# USB-nano.net
KiCad netlist of a schematic drawn in EAGLE
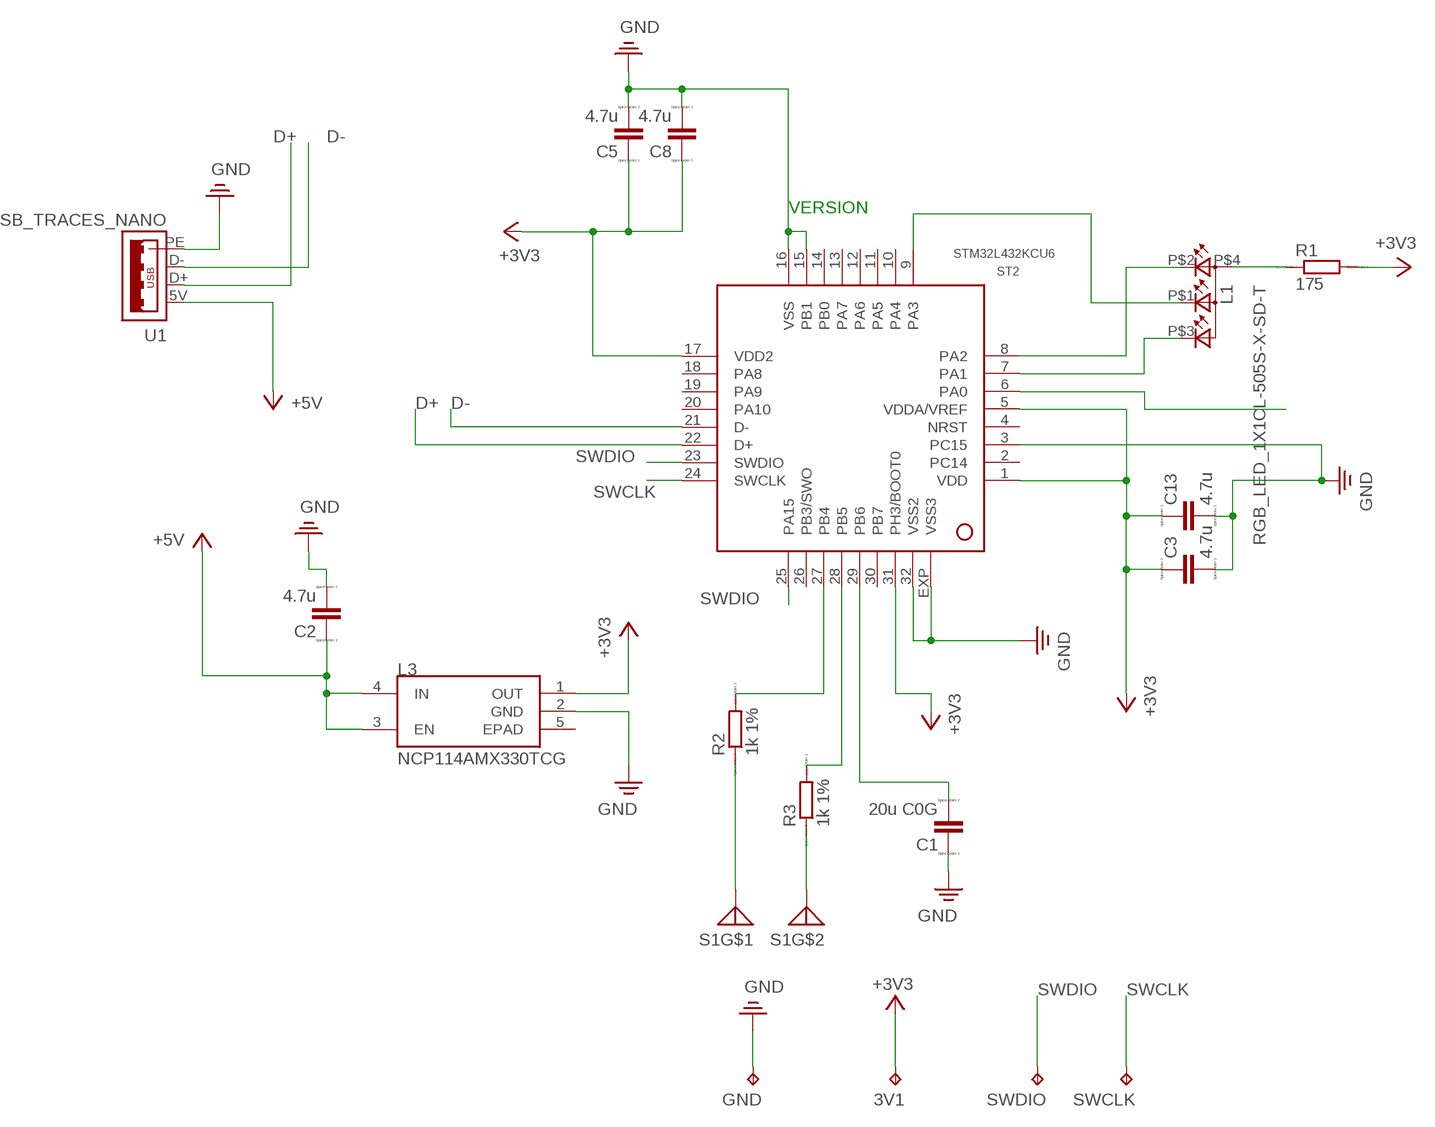
[diagram p0: schematic, sheet 1]

(export (version "E")
  (design (tool "Eeschema 10.0.6"))
  (components
    (comp (ref "3V1")
      (value "TEST_POINT")
      (footprint "eagle-import:B1,27")
      (libsource (lib "eagle-import") (part "TEST_POINT"))
    )
    (comp (ref "C1")
      (value "20u C0G")
      (footprint "eagle-import:C0402")
      (libsource (lib "eagle-import") (part "CAPACITOR"))
    )
    (comp (ref "C2")
      (value "4.7u")
      (footprint "eagle-import:C0402")
      (libsource (lib "eagle-import") (part "CAPACITOR"))
    )
    (comp (ref "C3")
      (value "4.7u")
      (footprint "eagle-import:C0402")
      (libsource (lib "eagle-import") (part "CAPACITOR"))
    )
    (comp (ref "C5")
      (value "4.7u")
      (footprint "eagle-import:C0402")
      (libsource (lib "eagle-import") (part "CAPACITOR"))
    )
    (comp (ref "C8")
      (value "4.7u")
      (footprint "eagle-import:C0402")
      (libsource (lib "eagle-import") (part "CAPACITOR"))
    )
    (comp (ref "C13")
      (value "4.7u")
      (footprint "eagle-import:C0402")
      (libsource (lib "eagle-import") (part "CAPACITOR"))
    )
    (comp (ref "GND")
      (value "TEST_POINT")
      (footprint "eagle-import:B1,27")
      (libsource (lib "eagle-import") (part "TEST_POINT"))
    )
    (comp (ref "L1")
      (value "RGB_LED_1X1CL-505S-X-SD-T")
      (footprint "eagle-import:CL-505S-X-SD-T")
      (libsource (lib "eagle-import") (part "RGB_LED_1X1CL-505S-X-SD-T"))
    )
    (comp (ref "L3")
      (value "NCP114AMX330TCG")
      (footprint "eagle-import:REG_NCP114AMX330TCG")
      (fields (field (name "MF") "ON Semiconductor"))
      (libsource (lib "eagle-import") (part "NCP114AMX330TCG"))
    )
    (comp (ref "R1")
      (value "175")
      (footprint "eagle-import:R0402")
      (libsource (lib "eagle-import") (part "RESISTOR"))
    )
    (comp (ref "R2")
      (value "1k 1%")
      (footprint "eagle-import:R0402")
      (libsource (lib "eagle-import") (part "RESISTOR"))
    )
    (comp (ref "R3")
      (value "1k 1%")
      (footprint "eagle-import:R0402")
      (libsource (lib "eagle-import") (part "RESISTOR"))
    )
    (comp (ref "S1")
      (value "TOUCH_SENSOR")
      (footprint "eagle-import:SOMU_CAPACITIVE_TOUCH_PAD")
      (libsource (lib "eagle-import") (part "TOUCH_SENSOR"))
    )
    (comp (ref "ST2")
      (value "STM32L432KCU6")
      (footprint "eagle-import:QFN32")
      (libsource (lib "eagle-import") (part "STM32L432KCU6"))
    )
    (comp (ref "SWCLK")
      (value "TEST_POINT")
      (footprint "eagle-import:B1,27")
      (libsource (lib "eagle-import") (part "TEST_POINT"))
    )
    (comp (ref "SWDIO")
      (value "TEST_POINT")
      (footprint "eagle-import:B1,27")
      (libsource (lib "eagle-import") (part "TEST_POINT"))
    )
    (comp (ref "U1")
      (value "USB_TRACES_NANO")
      (footprint "eagle-import:USB_TRACES_NANO")
      (libsource (lib "eagle-import") (part "USB_TRACES_NANO"))
    )
  )
  (nets
    (net (code "1") (name "+3V3") (class "Default")
      (node (ref "3V1") (pin "TP") (pinfunction "TP_TP") (pintype "input"))
      (node (ref "C13") (pin "1") (pinfunction "1_1") (pintype "passive"))
      (node (ref "C3") (pin "1") (pinfunction "1_1") (pintype "passive"))
      (node (ref "C5") (pin "1") (pinfunction "1_1") (pintype "passive"))
      (node (ref "C8") (pin "1") (pinfunction "1_1") (pintype "passive"))
      (node (ref "L3") (pin "1") (pinfunction "OUT_1") (pintype "output"))
      (node (ref "R1") (pin "2") (pinfunction "2_2") (pintype "passive"))
      (node (ref "ST2") (pin "1") (pinfunction "VDD_1") (pintype "bidirectional"))
      (node (ref "ST2") (pin "17") (pinfunction "VDD2_17") (pintype "bidirectional"))
      (node (ref "ST2") (pin "31") (pinfunction "PH3/BOOT0_31") (pintype "bidirectional"))
      (node (ref "ST2") (pin "5") (pinfunction "VDDA/VREF_5") (pintype "bidirectional"))
    )
    (net (code "2") (name "+5V") (class "Default")
      (node (ref "C2") (pin "1") (pinfunction "1_1") (pintype "passive"))
      (node (ref "L3") (pin "3") (pinfunction "EN_3") (pintype "input"))
      (node (ref "L3") (pin "4") (pinfunction "IN_4") (pintype "input"))
      (node (ref "U1") (pin "5V") (pinfunction "1_5V") (pintype "passive"))
    )
    (net (code "3") (name "/D+") (class "Default")
      (node (ref "ST2") (pin "22") (pinfunction "D+_22") (pintype "bidirectional"))
      (node (ref "U1") (pin "D+") (pinfunction "2_D+") (pintype "passive"))
    )
    (net (code "4") (name "/D-") (class "Default")
      (node (ref "ST2") (pin "21") (pinfunction "D-_21") (pintype "bidirectional"))
      (node (ref "U1") (pin "D-") (pinfunction "3_D-") (pintype "passive"))
    )
    (net (code "5") (name "/SWCLK") (class "Default")
      (node (ref "ST2") (pin "24") (pinfunction "SWCLK_24") (pintype "bidirectional"))
      (node (ref "SWCLK") (pin "TP") (pinfunction "TP_TP") (pintype "input"))
    )
    (net (code "6") (name "/SWDIO") (class "Default")
      (node (ref "ST2") (pin "23") (pinfunction "SWDIO_23") (pintype "bidirectional"))
      (node (ref "ST2") (pin "25") (pinfunction "PA15_25") (pintype "bidirectional"))
      (node (ref "SWDIO") (pin "TP") (pinfunction "TP_TP") (pintype "input"))
    )
    (net (code "7") (name "GND") (class "Default")
      (node (ref "C1") (pin "1") (pinfunction "1_1") (pintype "passive"))
      (node (ref "C13") (pin "2") (pinfunction "2_2") (pintype "passive"))
      (node (ref "C2") (pin "2") (pinfunction "2_2") (pintype "passive"))
      (node (ref "C3") (pin "2") (pinfunction "2_2") (pintype "passive"))
      (node (ref "C5") (pin "2") (pinfunction "2_2") (pintype "passive"))
      (node (ref "C8") (pin "2") (pinfunction "2_2") (pintype "passive"))
      (node (ref "GND") (pin "TP") (pinfunction "TP_TP") (pintype "input"))
      (node (ref "L3") (pin "2") (pinfunction "GND_2") (pintype "power_in"))
      (node (ref "ST2") (pin "15") (pinfunction "PB1_15") (pintype "bidirectional"))
      (node (ref "ST2") (pin "16") (pinfunction "VSS_16") (pintype "bidirectional"))
      (node (ref "ST2") (pin "3") (pinfunction "PC15_3") (pintype "bidirectional"))
      (node (ref "ST2") (pin "32") (pinfunction "VSS2_32") (pintype "bidirectional"))
      (node (ref "ST2") (pin "EXP") (pinfunction "VSS3_EXP") (pintype "bidirectional"))
      (node (ref "U1") (pin "PE") (pinfunction "4_PE") (pintype "passive"))
    )
    (net (code "8") (name "Net-(L1-A2)") (class "Default")
      (node (ref "L1") (pin "P$4") (pinfunction "A2_P$4") (pintype "passive"))
      (node (ref "R1") (pin "1") (pinfunction "1_1") (pintype "passive"))
    )
    (net (code "9") (name "Net-(L1-CBLUE)") (class "Default")
      (node (ref "L1") (pin "P$1") (pinfunction "CBLUE_P$1") (pintype "passive"))
      (node (ref "ST2") (pin "9") (pinfunction "PA3_9") (pintype "bidirectional"))
    )
    (net (code "10") (name "Net-(L1-CGREEN)") (class "Default")
      (node (ref "L1") (pin "P$3") (pinfunction "CGREEN_P$3") (pintype "passive"))
      (node (ref "ST2") (pin "7") (pinfunction "PA1_7") (pintype "bidirectional"))
    )
    (net (code "11") (name "Net-(L1-CRED)") (class "Default")
      (node (ref "L1") (pin "P$2") (pinfunction "CRED_P$2") (pintype "passive"))
      (node (ref "ST2") (pin "8") (pinfunction "PA2_8") (pintype "bidirectional"))
    )
    (net (code "12") (name "Net-(R2-Pad1)") (class "Default")
      (node (ref "R2") (pin "1") (pinfunction "1_1") (pintype "passive"))
      (node (ref "S1") (pin "P$1") (pinfunction "1_P$1") (pintype "output"))
      (node (ref "S1") (pin "SENSE") (pinfunction "1_SENSE") (pintype "output"))
    )
    (net (code "13") (name "Net-(R3-Pad1)") (class "Default")
      (node (ref "R3") (pin "1") (pinfunction "1_1") (pintype "passive"))
      (node (ref "S1") (pin "P$2") (pinfunction "1_P$2") (pintype "output"))
      (node (ref "S1") (pin "SENSE2") (pinfunction "1_SENSE2") (pintype "output"))
    )
    (net (code "14") (name "Net-(ST2-PB4)") (class "Default")
      (node (ref "R2") (pin "2") (pinfunction "2_2") (pintype "passive"))
      (node (ref "ST2") (pin "27") (pinfunction "PB4_27") (pintype "bidirectional"))
    )
    (net (code "15") (name "Net-(ST2-PB5)") (class "Default")
      (node (ref "R3") (pin "2") (pinfunction "2_2") (pintype "passive"))
      (node (ref "ST2") (pin "28") (pinfunction "PB5_28") (pintype "bidirectional"))
    )
    (net (code "16") (name "Net-(ST2-PB6)") (class "Default")
      (node (ref "C1") (pin "2") (pinfunction "2_2") (pintype "passive"))
      (node (ref "ST2") (pin "29") (pinfunction "PB6_29") (pintype "bidirectional"))
    )
    (net (code "17") (name "unconnected-(L3-EPAD-Pad5)") (class "Default")
      (node (ref "L3") (pin "5") (pinfunction "EPAD_5") (pintype "passive"))
    )
    (net (code "18") (name "unconnected-(ST2-NRST-Pad4)") (class "Default")
      (node (ref "ST2") (pin "4") (pinfunction "NRST_4") (pintype "bidirectional"))
    )
    (net (code "19") (name "unconnected-(ST2-PA0-Pad6)") (class "Default")
      (node (ref "ST2") (pin "6") (pinfunction "PA0_6") (pintype "bidirectional"))
    )
    (net (code "20") (name "unconnected-(ST2-PA4-Pad10)") (class "Default")
      (node (ref "ST2") (pin "10") (pinfunction "PA4_10") (pintype "bidirectional"))
    )
    (net (code "21") (name "unconnected-(ST2-PA5-Pad11)") (class "Default")
      (node (ref "ST2") (pin "11") (pinfunction "PA5_11") (pintype "bidirectional"))
    )
    (net (code "22") (name "unconnected-(ST2-PA6-Pad12)") (class "Default")
      (node (ref "ST2") (pin "12") (pinfunction "PA6_12") (pintype "bidirectional"))
    )
    (net (code "23") (name "unconnected-(ST2-PA7-Pad13)") (class "Default")
      (node (ref "ST2") (pin "13") (pinfunction "PA7_13") (pintype "bidirectional"))
    )
    (net (code "24") (name "unconnected-(ST2-PA8-Pad18)") (class "Default")
      (node (ref "ST2") (pin "18") (pinfunction "PA8_18") (pintype "bidirectional"))
    )
    (net (code "25") (name "unconnected-(ST2-PA9-Pad19)") (class "Default")
      (node (ref "ST2") (pin "19") (pinfunction "PA9_19") (pintype "bidirectional"))
    )
    (net (code "26") (name "unconnected-(ST2-PA10-Pad20)") (class "Default")
      (node (ref "ST2") (pin "20") (pinfunction "PA10_20") (pintype "bidirectional"))
    )
    (net (code "27") (name "unconnected-(ST2-PB0-Pad14)") (class "Default")
      (node (ref "ST2") (pin "14") (pinfunction "PB0_14") (pintype "bidirectional"))
    )
    (net (code "28") (name "unconnected-(ST2-PB3{slash}SWO-Pad26)") (class "Default")
      (node (ref "ST2") (pin "26") (pinfunction "PB3/SWO_26") (pintype "bidirectional"))
    )
    (net (code "29") (name "unconnected-(ST2-PB7-Pad30)") (class "Default")
      (node (ref "ST2") (pin "30") (pinfunction "PB7_30") (pintype "bidirectional"))
    )
    (net (code "30") (name "unconnected-(ST2-PC14-Pad2)") (class "Default")
      (node (ref "ST2") (pin "2") (pinfunction "PC14_2") (pintype "bidirectional"))
    )
  )
)
